# Motor_Connection.net
KiCad netlist of a schematic drawn in Altium Designer
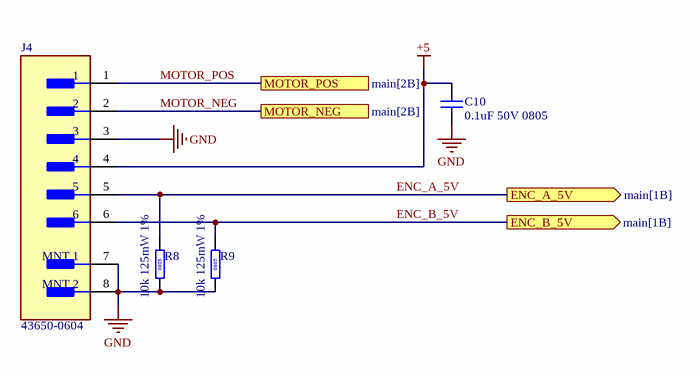
[diagram p0: Motor_Connection.SchDoc]

(export (version "E")
  (design (tool "Eeschema 10.0.6"))
  (components
    (comp (ref "C10")
      (value "0.1uF 50V 0805")
      (footprint "CAPC2012X14N")
      (description "Cap, SMD, 0.1uF, 50V, 10%, 0805, X7R")
      (fields
        (field (name "MANUFACTURER") "Samsung")
        (field (name "MANUFACTURERPARTNUMBER") "CL21B104KBCWPNC")
      )
      (libsource (lib "Andor Technology") (part "CAP"))
    )
    (comp (ref "J4")
      (value "43650-0604")
      (footprint "FP-43650-0604-MFG")
      (description "43650-0604 Conn Power HDR 6 POS 3mm Solder RA Thru-Hole 6 Terminal 1 Port Micro-Fit 3.0™ Frame")
      (libsource (lib "Altium Content Vault") (part "ed24c53d9ba001d1a2a686240a95171"))
    )
    (comp (ref "R8")
      (value "10k 125mW 1%")
      (footprint "RESC2013X60X35ML10T20")
      (description "Res, SMD, 10k, 125mW, 1%, ±200ppm, 0805")
      (fields
        (field (name "MANUFACTURER") "Panasonic")
        (field (name "MANUFACTURERPARTNUMBER") "ERJ-6GEYJ103V")
      )
      (libsource (lib "Andor Technology") (part "Resistor_0805"))
    )
    (comp (ref "R9")
      (value "10k 125mW 1%")
      (footprint "RESC2013X60X35ML10T20")
      (description "Res, SMD, 10k, 125mW, 1%, ±200ppm, 0805")
      (fields
        (field (name "MANUFACTURER") "Panasonic")
        (field (name "MANUFACTURERPARTNUMBER") "ERJ-6GEYJ103V")
      )
      (libsource (lib "Andor Technology") (part "Resistor_0805"))
    )
  )
  (nets
    (net (code "1") (name "+5") (class "Default")
      (node (ref "C10") (pin "2") (pinfunction "2_2") (pintype "passive"))
      (node (ref "J4") (pin "4") (pinfunction "4_4") (pintype "passive"))
    )
    (net (code "2") (name "/ENC_A_5V") (class "Default")
      (node (ref "J4") (pin "5") (pinfunction "5_5") (pintype "passive"))
      (node (ref "R8") (pin "2") (pinfunction "2_2") (pintype "passive"))
    )
    (net (code "3") (name "/ENC_B_5V") (class "Default")
      (node (ref "J4") (pin "6") (pinfunction "6_6") (pintype "passive"))
      (node (ref "R9") (pin "2") (pinfunction "2_2") (pintype "passive"))
    )
    (net (code "4") (name "/MOTOR_NEG") (class "Default")
      (node (ref "J4") (pin "2") (pinfunction "2_2") (pintype "passive"))
    )
    (net (code "5") (name "/MOTOR_POS") (class "Default")
      (node (ref "J4") (pin "1") (pinfunction "1_1") (pintype "passive"))
    )
    (net (code "6") (name "GND") (class "Default")
      (node (ref "C10") (pin "1") (pinfunction "1_1") (pintype "passive"))
      (node (ref "J4") (pin "3") (pinfunction "3_3") (pintype "passive"))
      (node (ref "J4") (pin "7") (pinfunction "MNT_1_7") (pintype "passive"))
      (node (ref "J4") (pin "8") (pinfunction "MNT_2_8") (pintype "passive"))
      (node (ref "R8") (pin "1") (pinfunction "1_1") (pintype "passive"))
      (node (ref "R9") (pin "1") (pinfunction "1_1") (pintype "passive"))
    )
  )
)
